# STl-Link-V303.net
KiCad netlist of a schematic drawn in EAGLE
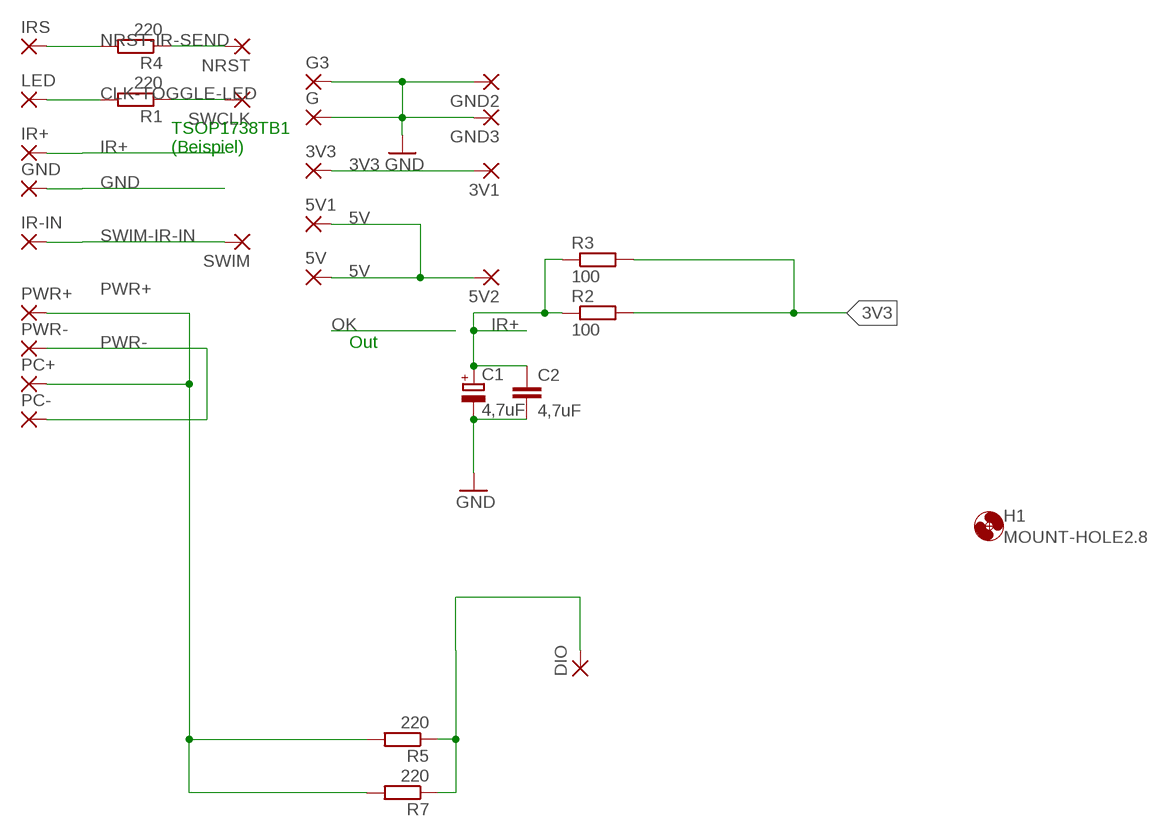
[diagram p0: schematic, sheet 1]

(export (version "E")
  (design (tool "Eeschema 10.0.6"))
  (components
    (comp (ref "3V1")
      (value "SMD2")
      (footprint "eagle-import:SMD1,27-2,54")
      (libsource (lib "eagle-import") (part "SMD2"))
    )
    (comp (ref "3V3")
      (value "SMD2")
      (footprint "eagle-import:SMD1,27-2,54")
      (libsource (lib "eagle-import") (part "SMD2"))
    )
    (comp (ref "5V")
      (value "SMD2")
      (footprint "eagle-import:SMD1,27-2,54")
      (libsource (lib "eagle-import") (part "SMD2"))
    )
    (comp (ref "5V1")
      (value "SMD2")
      (footprint "eagle-import:SMD1,27-2,54")
      (libsource (lib "eagle-import") (part "SMD2"))
    )
    (comp (ref "5V2")
      (value "SMD2")
      (footprint "eagle-import:SMD1,27-2,54")
      (libsource (lib "eagle-import") (part "SMD2"))
    )
    (comp (ref "C1")
      (value "4,7uF")
      (footprint "eagle-import:E1,8-4")
      (libsource (lib "eagle-import") (part "CPOL-EUE1.8-4"))
    )
    (comp (ref "C2")
      (value "4,7uF")
      (footprint "eagle-import:C1206K")
      (libsource (lib "eagle-import") (part "C-EUC1206K"))
    )
    (comp (ref "DIO")
      (value "SMD2")
      (footprint "eagle-import:SMD1,27-2,54")
      (libsource (lib "eagle-import") (part "SMD2"))
    )
    (comp (ref "G")
      (value "SMD2")
      (footprint "eagle-import:SMD1,27-2,54")
      (libsource (lib "eagle-import") (part "SMD2"))
    )
    (comp (ref "G3")
      (value "SMD2")
      (footprint "eagle-import:SMD1,27-2,54")
      (libsource (lib "eagle-import") (part "SMD2"))
    )
    (comp (ref "GND")
      (value "SMD2")
      (footprint "eagle-import:SMD1,27-2,54")
      (libsource (lib "eagle-import") (part "SMD2"))
    )
    (comp (ref "GND2")
      (value "SMD2")
      (footprint "eagle-import:SMD1,27-2,54")
      (libsource (lib "eagle-import") (part "SMD2"))
    )
    (comp (ref "GND3")
      (value "SMD2")
      (footprint "eagle-import:SMD1,27-2,54")
      (libsource (lib "eagle-import") (part "SMD2"))
    )
    (comp (ref "H1")
      (value "MOUNT-HOLE2.8")
      (footprint "eagle-import:2,8")
      (libsource (lib "eagle-import") (part "MOUNT-HOLE2.8"))
    )
    (comp (ref "IR+")
      (value "SMD2")
      (footprint "eagle-import:SMD1,27-2,54")
      (libsource (lib "eagle-import") (part "SMD2"))
    )
    (comp (ref "IR-IN")
      (value "SMD2")
      (footprint "eagle-import:SMD1,27-2,54")
      (libsource (lib "eagle-import") (part "SMD2"))
    )
    (comp (ref "IRS")
      (value "SMD2")
      (footprint "eagle-import:SMD1,27-2,54")
      (libsource (lib "eagle-import") (part "SMD2"))
    )
    (comp (ref "LED")
      (value "SMD2")
      (footprint "eagle-import:SMD1,27-2,54")
      (libsource (lib "eagle-import") (part "SMD2"))
    )
    (comp (ref "NRST")
      (value "SMD2")
      (footprint "eagle-import:SMD1,27-2,54")
      (libsource (lib "eagle-import") (part "SMD2"))
    )
    (comp (ref "PC+")
      (value "SMD2")
      (footprint "eagle-import:SMD1,27-2,54")
      (libsource (lib "eagle-import") (part "SMD2"))
    )
    (comp (ref "PC-")
      (value "SMD2")
      (footprint "eagle-import:SMD1,27-2,54")
      (libsource (lib "eagle-import") (part "SMD2"))
    )
    (comp (ref "PWR+")
      (value "SMD2")
      (footprint "eagle-import:SMD1,27-2,54")
      (libsource (lib "eagle-import") (part "SMD2"))
    )
    (comp (ref "PWR-")
      (value "SMD2")
      (footprint "eagle-import:SMD1,27-2,54")
      (libsource (lib "eagle-import") (part "SMD2"))
    )
    (comp (ref "R1")
      (value "220")
      (footprint "eagle-import:R0805W")
      (libsource (lib "eagle-import") (part "R-EU_R0805W"))
    )
    (comp (ref "R2")
      (value "100")
      (footprint "eagle-import:0204_7")
      (libsource (lib "eagle-import") (part "R-EU_0204/7"))
    )
    (comp (ref "R3")
      (value "100")
      (footprint "eagle-import:R0805W")
      (libsource (lib "eagle-import") (part "R-EU_R0805W"))
    )
    (comp (ref "R4")
      (value "220")
      (footprint "eagle-import:R0805W")
      (libsource (lib "eagle-import") (part "R-EU_R0805W"))
    )
    (comp (ref "R5")
      (value "220")
      (footprint "eagle-import:0204_7")
      (libsource (lib "eagle-import") (part "R-EU_0204/7"))
    )
    (comp (ref "R7")
      (value "220")
      (footprint "eagle-import:R0805W")
      (libsource (lib "eagle-import") (part "R-EU_R0805W"))
    )
    (comp (ref "SWCLK")
      (value "SMD2")
      (footprint "eagle-import:SMD1,27-2,54")
      (libsource (lib "eagle-import") (part "SMD2"))
    )
    (comp (ref "SWIM")
      (value "SMD2")
      (footprint "eagle-import:SMD1,27-2,54")
      (libsource (lib "eagle-import") (part "SMD2"))
    )
  )
  (nets
    (net (code "1") (name "/5V") (class "Default")
      (node (ref "5V") (pin "1") (pinfunction "P_1") (pintype "passive"))
      (node (ref "5V1") (pin "1") (pinfunction "P_1") (pintype "passive"))
      (node (ref "5V2") (pin "1") (pinfunction "P_1") (pintype "passive"))
    )
    (net (code "2") (name "/CLK-TOGGLE-LED") (class "Default")
      (node (ref "R1") (pin "1") (pinfunction "1_1") (pintype "passive"))
      (node (ref "SWCLK") (pin "1") (pinfunction "P_1") (pintype "passive"))
    )
    (net (code "3") (name "/IR+") (class "Default")
      (node (ref "C1") (pin "+") (pinfunction "+_+") (pintype "passive"))
      (node (ref "C2") (pin "1") (pinfunction "1_1") (pintype "passive"))
      (node (ref "IR+") (pin "1") (pinfunction "P_1") (pintype "passive"))
      (node (ref "R2") (pin "1") (pinfunction "1_1") (pintype "passive"))
      (node (ref "R3") (pin "1") (pinfunction "1_1") (pintype "passive"))
    )
    (net (code "4") (name "/NRST-IR-SEND") (class "Default")
      (node (ref "IRS") (pin "1") (pinfunction "P_1") (pintype "passive"))
      (node (ref "R4") (pin "2") (pinfunction "2_2") (pintype "passive"))
    )
    (net (code "6") (name "/PWR+") (class "Default")
      (node (ref "PC+") (pin "1") (pinfunction "P_1") (pintype "passive"))
      (node (ref "PWR+") (pin "1") (pinfunction "P_1") (pintype "passive"))
      (node (ref "R5") (pin "2") (pinfunction "2_2") (pintype "passive"))
      (node (ref "R7") (pin "2") (pinfunction "2_2") (pintype "passive"))
    )
    (net (code "7") (name "/PWR-") (class "Default")
      (node (ref "PC-") (pin "1") (pinfunction "P_1") (pintype "passive"))
      (node (ref "PWR-") (pin "1") (pinfunction "P_1") (pintype "passive"))
    )
    (net (code "8") (name "/SWIM-IR-IN") (class "Default")
      (node (ref "IR-IN") (pin "1") (pinfunction "P_1") (pintype "passive"))
      (node (ref "SWIM") (pin "1") (pinfunction "P_1") (pintype "passive"))
    )
    (net (code "9") (name "3V3") (class "Default")
      (node (ref "3V1") (pin "1") (pinfunction "P_1") (pintype "passive"))
      (node (ref "3V3") (pin "1") (pinfunction "P_1") (pintype "passive"))
      (node (ref "R2") (pin "2") (pinfunction "2_2") (pintype "passive"))
      (node (ref "R3") (pin "2") (pinfunction "2_2") (pintype "passive"))
    )
    (net (code "10") (name "GND") (class "Default")
      (node (ref "C1") (pin "-") (pinfunction "-_-") (pintype "passive"))
      (node (ref "C2") (pin "2") (pinfunction "2_2") (pintype "passive"))
      (node (ref "G") (pin "1") (pinfunction "P_1") (pintype "passive"))
      (node (ref "G3") (pin "1") (pinfunction "P_1") (pintype "passive"))
      (node (ref "GND") (pin "1") (pinfunction "P_1") (pintype "passive"))
      (node (ref "GND2") (pin "1") (pinfunction "P_1") (pintype "passive"))
      (node (ref "GND3") (pin "1") (pinfunction "P_1") (pintype "passive"))
    )
    (net (code "11") (name "Net-(DIO-P)") (class "Default")
      (node (ref "DIO") (pin "1") (pinfunction "P_1") (pintype "passive"))
      (node (ref "R5") (pin "1") (pinfunction "1_1") (pintype "passive"))
      (node (ref "R7") (pin "1") (pinfunction "1_1") (pintype "passive"))
    )
    (net (code "12") (name "Net-(LED-P)") (class "Default")
      (node (ref "LED") (pin "1") (pinfunction "P_1") (pintype "passive"))
      (node (ref "R1") (pin "2") (pinfunction "2_2") (pintype "passive"))
    )
    (net (code "13") (name "Net-(NRST-P)") (class "Default")
      (node (ref "NRST") (pin "1") (pinfunction "P_1") (pintype "passive"))
      (node (ref "R4") (pin "1") (pinfunction "1_1") (pintype "passive"))
    )
  )
)
